# Main.net
KiCad netlist of a schematic drawn in Altium Designer
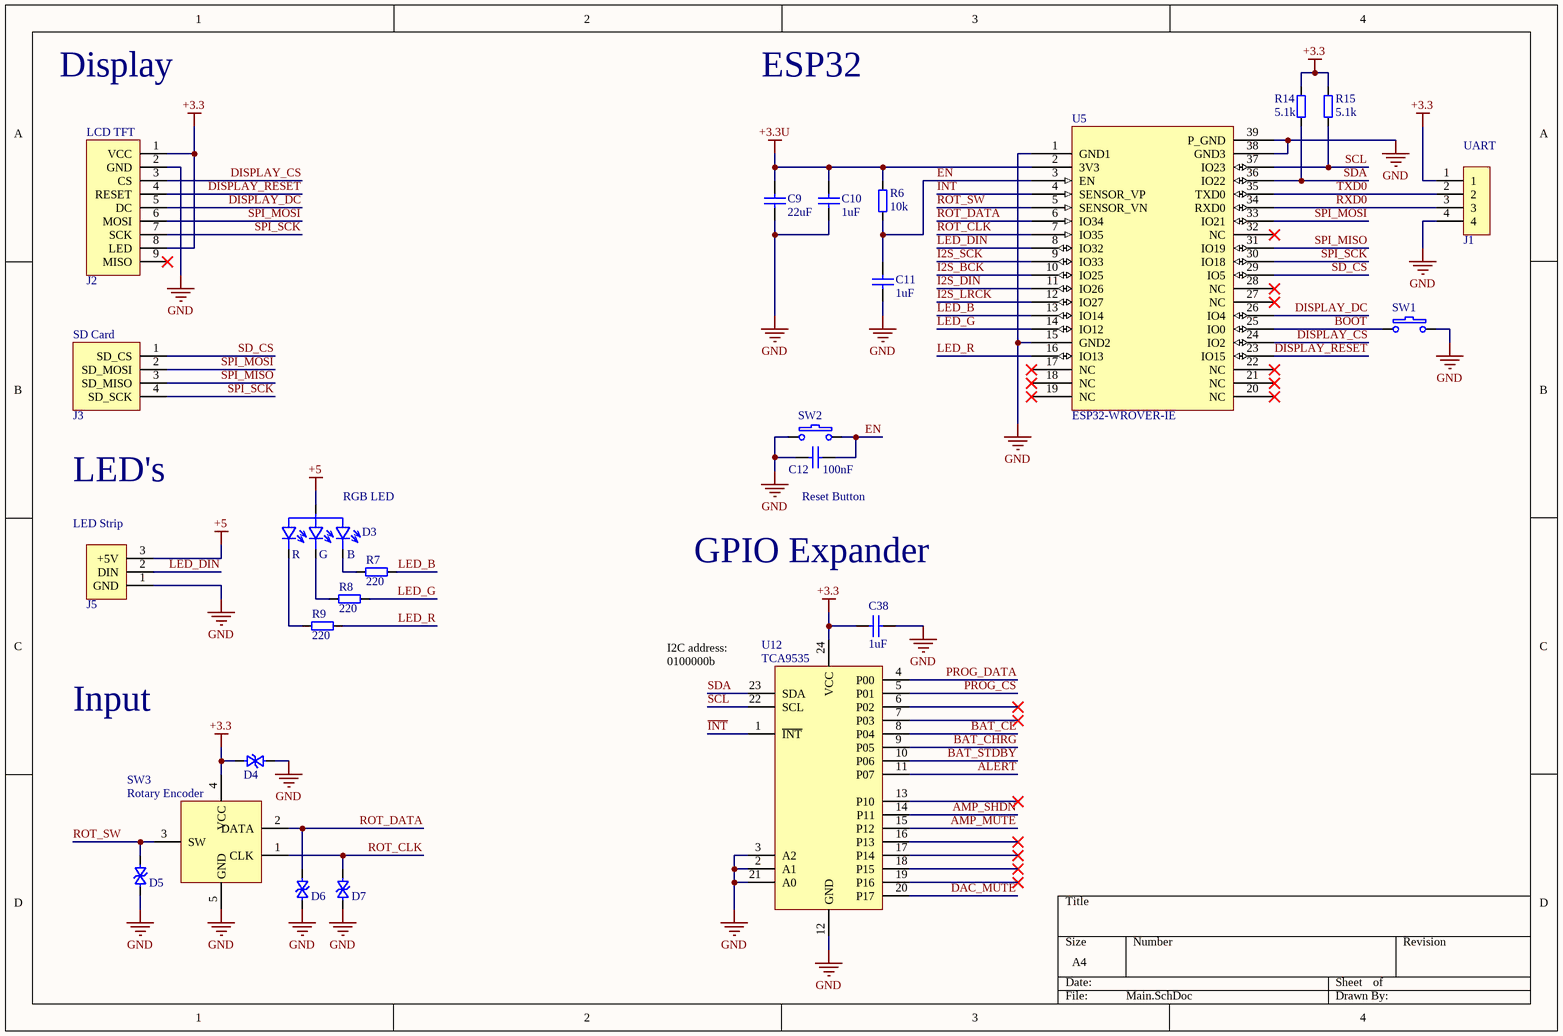
[diagram p0: Main.SchDoc]

(export (version "E")
  (design (tool "Eeschema 10.0.6"))
  (components
    (comp (ref "C9")
      (value "Capacitor_22uF")
      (footprint "CAP 0805")
      (fields (field (name "CAPACITANCE") "22uF"))
      (libsource (lib "BasicComponents") (part "Capacitor_22uF"))
    )
    (comp (ref "C10")
      (value "Capacitor_1uF")
      (footprint "CAP 0805")
      (fields (field (name "CAPACITANCE") "1uF"))
      (libsource (lib "BasicComponents") (part "Capacitor_1uF"))
    )
    (comp (ref "C11")
      (value "Capacitor_1uF")
      (footprint "CAP 0805")
      (fields (field (name "CAPACITANCE") "1uF"))
      (libsource (lib "BasicComponents") (part "Capacitor_1uF"))
    )
    (comp (ref "C12")
      (value "Capacitor_100nF")
      (footprint "CAP 0805")
      (fields (field (name "CAPACITANCE") "100nF"))
      (libsource (lib "BasicComponents") (part "Capacitor_100nF"))
    )
    (comp (ref "C38")
      (value "Capacitor_1uF")
      (footprint "CAP 0805")
      (fields (field (name "CAPACITANCE") "1uF"))
      (libsource (lib "BasicComponents") (part "Capacitor_1uF"))
    )
    (comp (ref "D3")
      (value "LED_RGB")
      (footprint "4Pin")
      (libsource (lib "BasicComponents") (part "LED_RGB"))
    )
    (comp (ref "D4")
      (value "Diode_TVS_Bi")
      (footprint "DIOM4226X24N")
      (libsource (lib "BasicComponents") (part "Diode_TVS_Bi"))
    )
    (comp (ref "D5")
      (value "Diode_TVS_Bi")
      (footprint "DIOM4226X24N")
      (libsource (lib "BasicComponents") (part "Diode_TVS_Bi"))
    )
    (comp (ref "D6")
      (value "Diode_TVS_Bi")
      (footprint "DIOM4226X24N")
      (libsource (lib "BasicComponents") (part "Diode_TVS_Bi"))
    )
    (comp (ref "D7")
      (value "Diode_TVS_Bi")
      (footprint "DIOM4226X24N")
      (libsource (lib "BasicComponents") (part "Diode_TVS_Bi"))
    )
    (comp (ref "J1")
      (value "1x4 Header")
      (footprint "1x4 Header")
      (libsource (lib "BasicConnectors") (part "1x4_Header"))
    )
    (comp (ref "J2")
      (value "1x4 Header")
      (footprint "1X9 HEADER")
      (libsource (lib "BasicConnectors") (part "1x9_Header TFT Screen"))
    )
    (comp (ref "J3")
      (value "1x4 Header")
      (footprint "1x4 Header")
      (libsource (lib "BasicConnectors") (part "1x4_Header SD Card"))
    )
    (comp (ref "J5")
      (value "1x3_Header")
      (footprint "1x3Header")
      (libsource (lib "BasicConnectors") (part "1x3_Header WS2812B"))
    )
    (comp (ref "R6")
      (value "Resistor_10k")
      (footprint "RES 0805")
      (fields (field (name "RESISTANCE") "10k"))
      (libsource (lib "BasicComponents") (part "Resistor_10k"))
    )
    (comp (ref "R7")
      (value "Resistor_220")
      (footprint "RES 0805")
      (fields (field (name "RESISTANCE") "220"))
      (libsource (lib "BasicComponents") (part "Resistor_220"))
    )
    (comp (ref "R8")
      (value "Resistor_220")
      (footprint "RES 0805")
      (fields (field (name "RESISTANCE") "220"))
      (libsource (lib "BasicComponents") (part "Resistor_220"))
    )
    (comp (ref "R9")
      (value "Resistor_220")
      (footprint "RES 0805")
      (fields (field (name "RESISTANCE") "220"))
      (libsource (lib "BasicComponents") (part "Resistor_220"))
    )
    (comp (ref "R14")
      (value "Resistor_5.1k")
      (footprint "RES 0805")
      (fields (field (name "RESISTANCE") "5.1k"))
      (libsource (lib "BasicComponents") (part "Resistor_5.1k"))
    )
    (comp (ref "R15")
      (value "Resistor_5.1k")
      (footprint "RES 0805")
      (fields (field (name "RESISTANCE") "5.1k"))
      (libsource (lib "") (part "Resistor_5.1k_1"))
    )
    (comp (ref "SW1")
      (value "Switch_PB")
      (footprint "2Pin")
      (libsource (lib "BasicComponents") (part "Switch_PB"))
    )
    (comp (ref "SW2")
      (value "Switch_PB")
      (footprint "2Pin")
      (libsource (lib "BasicComponents") (part "Switch_PB"))
    )
    (comp (ref "SW3")
      (value "Rotary Encoder")
      (footprint "1x5 Header")
      (libsource (lib "CustomModule") (part "Rotary Encoder"))
    )
    (comp (ref "U5")
      (value "ESP32-WROVER-IE")
      (footprint "ESP32 WROVER")
      (libsource (lib "Microcontrollers") (part "ESP32-WROVER-IE"))
    )
    (comp (ref "U12")
      (value "TCA9535")
      (footprint "TSOP65P640X120-24N")
      (description "I2C GPIO Expander")
      (libsource (lib "CustomModule") (part "TCA9535"))
    )
  )
  (nets
    (net (code "1") (name "+3.3") (class "Default")
      (node (ref "C38") (pin "2") (pintype "passive"))
      (node (ref "D4") (pin "1") (pintype "passive"))
      (node (ref "J1") (pin "1") (pinfunction "1_1") (pintype "passive"))
      (node (ref "J2") (pin "1") (pinfunction "VCC_1") (pintype "passive"))
      (node (ref "J2") (pin "8") (pinfunction "LED_8") (pintype "passive"))
      (node (ref "R14") (pin "2") (pintype "passive"))
      (node (ref "R15") (pin "2") (pintype "passive"))
      (node (ref "SW3") (pin "4") (pinfunction "VCC_4") (pintype "passive"))
      (node (ref "U12") (pin "24") (pinfunction "VCC_24") (pintype "passive"))
    )
    (net (code "2") (name "+3.3U") (class "Default")
      (node (ref "C10") (pin "2") (pintype "passive"))
      (node (ref "C9") (pin "2") (pintype "passive"))
      (node (ref "R6") (pin "2") (pintype "passive"))
      (node (ref "U5") (pin "2") (pinfunction "3V3_2") (pintype "power_in"))
    )
    (net (code "3") (name "+5") (class "Default")
      (node (ref "D3") (pin "2") (pinfunction "Anode_2") (pintype "passive"))
      (node (ref "J5") (pin "3") (pinfunction "+5V_3") (pintype "passive"))
    )
    (net (code "4") (name "/ALERT") (class "Default")
      (node (ref "U12") (pin "11") (pinfunction "P07_11") (pintype "passive"))
    )
    (net (code "5") (name "/AMP_~{MUTE}") (class "Default")
      (node (ref "U12") (pin "15") (pinfunction "P12_15") (pintype "passive"))
    )
    (net (code "6") (name "/AMP_~{SHDN}") (class "Default")
      (node (ref "U12") (pin "14") (pinfunction "P11_14") (pintype "passive"))
    )
    (net (code "7") (name "/BAT_CE") (class "Default")
      (node (ref "U12") (pin "8") (pinfunction "P04_8") (pintype "passive"))
    )
    (net (code "8") (name "/BAT_CHRG") (class "Default")
      (node (ref "U12") (pin "9") (pinfunction "P05_9") (pintype "passive"))
    )
    (net (code "9") (name "/BAT_STDBY") (class "Default")
      (node (ref "U12") (pin "10") (pinfunction "P06_10") (pintype "passive"))
    )
    (net (code "10") (name "/BOOT") (class "Default")
      (node (ref "SW1") (pin "1") (pintype "passive"))
      (node (ref "U5") (pin "25") (pinfunction "IO0_25") (pintype "bidirectional"))
    )
    (net (code "11") (name "/DAC_MUTE") (class "Default")
      (node (ref "U12") (pin "20") (pinfunction "P17_20") (pintype "passive"))
    )
    (net (code "12") (name "/DISPLAY_CS") (class "Default")
      (node (ref "J2") (pin "3") (pinfunction "CS_3") (pintype "passive"))
      (node (ref "U5") (pin "24") (pinfunction "IO2_24") (pintype "bidirectional"))
    )
    (net (code "13") (name "/DISPLAY_DC") (class "Default")
      (node (ref "J2") (pin "5") (pinfunction "DC_5") (pintype "passive"))
      (node (ref "U5") (pin "26") (pinfunction "IO4_26") (pintype "bidirectional"))
    )
    (net (code "14") (name "/DISPLAY_RESET") (class "Default")
      (node (ref "J2") (pin "4") (pinfunction "RESET_4") (pintype "passive"))
      (node (ref "U5") (pin "23") (pinfunction "IO15_23") (pintype "bidirectional"))
    )
    (net (code "15") (name "/EN") (class "Default")
      (node (ref "C11") (pin "2") (pintype "passive"))
      (node (ref "C12") (pin "2") (pintype "passive"))
      (node (ref "R6") (pin "1") (pintype "passive"))
      (node (ref "SW2") (pin "2") (pintype "passive"))
      (node (ref "U5") (pin "3") (pinfunction "EN_3") (pintype "input"))
    )
    (net (code "16") (name "/I2S_BCK") (class "Default")
      (node (ref "U5") (pin "10") (pinfunction "IO25_10") (pintype "bidirectional"))
    )
    (net (code "17") (name "/I2S_DIN") (class "Default")
      (node (ref "U5") (pin "11") (pinfunction "IO26_11") (pintype "bidirectional"))
    )
    (net (code "18") (name "/I2S_LRCK") (class "Default")
      (node (ref "U5") (pin "12") (pinfunction "IO27_12") (pintype "bidirectional"))
    )
    (net (code "19") (name "/I2S_SCK") (class "Default")
      (node (ref "U5") (pin "9") (pinfunction "IO33_9") (pintype "bidirectional"))
    )
    (net (code "20") (name "/LED_B") (class "Default")
      (node (ref "R7") (pin "1") (pintype "passive"))
      (node (ref "U5") (pin "13") (pinfunction "IO14_13") (pintype "bidirectional"))
    )
    (net (code "21") (name "/LED_DIN") (class "Default")
      (node (ref "J5") (pin "2") (pinfunction "DIN_2") (pintype "passive"))
      (node (ref "U5") (pin "8") (pinfunction "IO32_8") (pintype "bidirectional"))
    )
    (net (code "22") (name "/LED_G") (class "Default")
      (node (ref "R8") (pin "1") (pintype "passive"))
      (node (ref "U5") (pin "14") (pinfunction "IO12_14") (pintype "bidirectional"))
    )
    (net (code "23") (name "/LED_R") (class "Default")
      (node (ref "R9") (pin "1") (pintype "passive"))
      (node (ref "U5") (pin "16") (pinfunction "IO13_16") (pintype "bidirectional"))
    )
    (net (code "24") (name "/PROG_CS") (class "Default")
      (node (ref "U12") (pin "5") (pinfunction "P01_5") (pintype "passive"))
    )
    (net (code "25") (name "/PROG_DATA") (class "Default")
      (node (ref "U12") (pin "4") (pinfunction "P00_4") (pintype "passive"))
    )
    (net (code "26") (name "/ROT_CLK") (class "Default")
      (node (ref "D7") (pin "1") (pintype "passive"))
      (node (ref "SW3") (pin "1") (pinfunction "CLK_1") (pintype "passive"))
      (node (ref "U5") (pin "7") (pinfunction "IO35_7") (pintype "input"))
    )
    (net (code "27") (name "/ROT_DATA") (class "Default")
      (node (ref "D6") (pin "1") (pintype "passive"))
      (node (ref "SW3") (pin "2") (pinfunction "DATA_2") (pintype "passive"))
      (node (ref "U5") (pin "6") (pinfunction "IO34_6") (pintype "input"))
    )
    (net (code "28") (name "/ROT_SW") (class "Default")
      (node (ref "D5") (pin "1") (pintype "passive"))
      (node (ref "SW3") (pin "3") (pinfunction "SW_3") (pintype "passive"))
      (node (ref "U5") (pin "5") (pinfunction "SENSOR_VN_5") (pintype "input"))
    )
    (net (code "29") (name "/RXD0") (class "Default")
      (node (ref "J1") (pin "3") (pinfunction "3_3") (pintype "passive"))
      (node (ref "U5") (pin "34") (pinfunction "RXD0_34") (pintype "bidirectional"))
    )
    (net (code "30") (name "/SCL") (class "Default")
      (node (ref "R15") (pin "1") (pintype "passive"))
      (node (ref "U12") (pin "22") (pinfunction "SCL_22") (pintype "passive"))
      (node (ref "U5") (pin "37") (pinfunction "IO23_37") (pintype "bidirectional"))
    )
    (net (code "31") (name "/SDA") (class "Default")
      (node (ref "R14") (pin "1") (pintype "passive"))
      (node (ref "U12") (pin "23") (pinfunction "SDA_23") (pintype "passive"))
      (node (ref "U5") (pin "36") (pinfunction "IO22_36") (pintype "bidirectional"))
    )
    (net (code "32") (name "/SD_CS") (class "Default")
      (node (ref "J3") (pin "1") (pinfunction "SD_CS_1") (pintype "passive"))
      (node (ref "U5") (pin "29") (pinfunction "IO5_29") (pintype "bidirectional"))
    )
    (net (code "33") (name "/SPI_MISO") (class "Default")
      (node (ref "J3") (pin "3") (pinfunction "SD_MISO_3") (pintype "passive"))
      (node (ref "U5") (pin "31") (pinfunction "IO19_31") (pintype "bidirectional"))
    )
    (net (code "34") (name "/SPI_MOSI") (class "Default")
      (node (ref "J2") (pin "6") (pinfunction "MOSI_6") (pintype "passive"))
      (node (ref "J3") (pin "2") (pinfunction "SD_MOSI_2") (pintype "passive"))
      (node (ref "U5") (pin "33") (pinfunction "IO21_33") (pintype "bidirectional"))
    )
    (net (code "35") (name "/SPI_SCK") (class "Default")
      (node (ref "J2") (pin "7") (pinfunction "SCK_7") (pintype "passive"))
      (node (ref "J3") (pin "4") (pinfunction "SD_SCK_4") (pintype "passive"))
      (node (ref "U5") (pin "30") (pinfunction "IO18_30") (pintype "bidirectional"))
    )
    (net (code "36") (name "/TXD0") (class "Default")
      (node (ref "J1") (pin "2") (pinfunction "2_2") (pintype "passive"))
      (node (ref "U5") (pin "35") (pinfunction "TXD0_35") (pintype "bidirectional"))
    )
    (net (code "37") (name "/~{INT}") (class "Default")
      (node (ref "U12") (pin "1") (pinfunction "~{INT}_1") (pintype "passive"))
      (node (ref "U5") (pin "4") (pinfunction "SENSOR_VP_4") (pintype "input"))
    )
    (net (code "38") (name "GND") (class "Default")
      (node (ref "C10") (pin "1") (pintype "passive"))
      (node (ref "C11") (pin "1") (pintype "passive"))
      (node (ref "C12") (pin "1") (pintype "passive"))
      (node (ref "C38") (pin "1") (pintype "passive"))
      (node (ref "C9") (pin "1") (pintype "passive"))
      (node (ref "D4") (pin "2") (pintype "passive"))
      (node (ref "D5") (pin "2") (pintype "passive"))
      (node (ref "D6") (pin "2") (pintype "passive"))
      (node (ref "D7") (pin "2") (pintype "passive"))
      (node (ref "J1") (pin "4") (pinfunction "4_4") (pintype "passive"))
      (node (ref "J2") (pin "2") (pinfunction "GND_2") (pintype "passive"))
      (node (ref "J5") (pin "1") (pinfunction "GND_1") (pintype "passive"))
      (node (ref "SW1") (pin "2") (pintype "passive"))
      (node (ref "SW2") (pin "1") (pintype "passive"))
      (node (ref "SW3") (pin "5") (pinfunction "GND_5") (pintype "passive"))
      (node (ref "U12") (pin "12") (pinfunction "GND_12") (pintype "passive"))
      (node (ref "U12") (pin "2") (pinfunction "A1_2") (pintype "passive"))
      (node (ref "U12") (pin "21") (pinfunction "A0_21") (pintype "passive"))
      (node (ref "U12") (pin "3") (pinfunction "A2_3") (pintype "passive"))
      (node (ref "U5") (pin "1") (pinfunction "GND1_1") (pintype "power_in"))
      (node (ref "U5") (pin "15") (pinfunction "GND2_15") (pintype "power_in"))
      (node (ref "U5") (pin "38") (pinfunction "GND3_38") (pintype "power_in"))
      (node (ref "U5") (pin "39") (pinfunction "P_GND_39") (pintype "power_in"))
    )
    (net (code "39") (name "Net-(D3-Blue)") (class "Default")
      (node (ref "D3") (pin "4") (pinfunction "Blue_4") (pintype "passive"))
      (node (ref "R7") (pin "2") (pintype "passive"))
    )
    (net (code "40") (name "Net-(D3-Green)") (class "Default")
      (node (ref "D3") (pin "3") (pinfunction "Green_3") (pintype "passive"))
      (node (ref "R8") (pin "2") (pintype "passive"))
    )
    (net (code "41") (name "Net-(D3-Red)") (class "Default")
      (node (ref "D3") (pin "1") (pinfunction "Red_1") (pintype "passive"))
      (node (ref "R9") (pin "2") (pintype "passive"))
    )
    (net (code "42") (name "unconnected-(J2-MISO-Pad9)") (class "Default")
      (node (ref "J2") (pin "9") (pinfunction "MISO_9") (pintype "passive+no_connect"))
    )
    (net (code "43") (name "unconnected-(U5-NC-Pad17)") (class "Default")
      (node (ref "U5") (pin "17") (pinfunction "NC_17") (pintype "tri_state+no_connect"))
    )
    (net (code "44") (name "unconnected-(U5-NC-Pad18)") (class "Default")
      (node (ref "U5") (pin "18") (pinfunction "NC_18") (pintype "tri_state+no_connect"))
    )
    (net (code "45") (name "unconnected-(U5-NC-Pad19)") (class "Default")
      (node (ref "U5") (pin "19") (pinfunction "NC_19") (pintype "tri_state+no_connect"))
    )
    (net (code "46") (name "unconnected-(U5-NC-Pad20)") (class "Default")
      (node (ref "U5") (pin "20") (pinfunction "NC_20") (pintype "tri_state+no_connect"))
    )
    (net (code "47") (name "unconnected-(U5-NC-Pad21)") (class "Default")
      (node (ref "U5") (pin "21") (pinfunction "NC_21") (pintype "tri_state+no_connect"))
    )
    (net (code "48") (name "unconnected-(U5-NC-Pad22)") (class "Default")
      (node (ref "U5") (pin "22") (pinfunction "NC_22") (pintype "tri_state+no_connect"))
    )
    (net (code "49") (name "unconnected-(U5-NC-Pad27)") (class "Default")
      (node (ref "U5") (pin "27") (pinfunction "NC_27") (pintype "tri_state+no_connect"))
    )
    (net (code "50") (name "unconnected-(U5-NC-Pad28)") (class "Default")
      (node (ref "U5") (pin "28") (pinfunction "NC_28") (pintype "tri_state+no_connect"))
    )
    (net (code "51") (name "unconnected-(U5-NC-Pad32)") (class "Default")
      (node (ref "U5") (pin "32") (pinfunction "NC_32") (pintype "tri_state+no_connect"))
    )
    (net (code "52") (name "unconnected-(U12-P02-Pad6)") (class "Default")
      (node (ref "U12") (pin "6") (pinfunction "P02_6") (pintype "passive+no_connect"))
    )
    (net (code "53") (name "unconnected-(U12-P03-Pad7)") (class "Default")
      (node (ref "U12") (pin "7") (pinfunction "P03_7") (pintype "passive+no_connect"))
    )
    (net (code "54") (name "unconnected-(U12-P10-Pad13)") (class "Default")
      (node (ref "U12") (pin "13") (pinfunction "P10_13") (pintype "passive+no_connect"))
    )
    (net (code "55") (name "unconnected-(U12-P13-Pad16)") (class "Default")
      (node (ref "U12") (pin "16") (pinfunction "P13_16") (pintype "passive+no_connect"))
    )
    (net (code "56") (name "unconnected-(U12-P14-Pad17)") (class "Default")
      (node (ref "U12") (pin "17") (pinfunction "P14_17") (pintype "passive+no_connect"))
    )
    (net (code "57") (name "unconnected-(U12-P15-Pad18)") (class "Default")
      (node (ref "U12") (pin "18") (pinfunction "P15_18") (pintype "passive+no_connect"))
    )
    (net (code "58") (name "unconnected-(U12-P16-Pad19)") (class "Default")
      (node (ref "U12") (pin "19") (pinfunction "P16_19") (pintype "passive+no_connect"))
    )
  )
)
